# led.net
KiCad netlist of a schematic drawn in Altium Designer
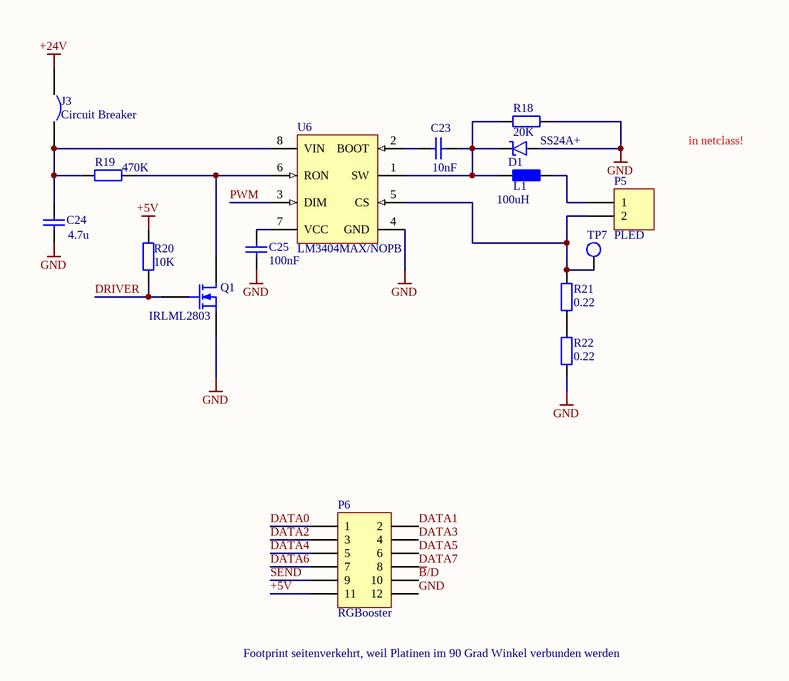
[diagram p0: led.SchDoc]

(export (version "E")
  (design (tool "Eeschema 10.0.6"))
  (components
    (comp (ref "C23")
      (value "10nF")
      (footprint "6-0805_M")
      (description "Capacitor")
      (fields (field (name "Comment") "Cap") (field (name "PUBLISHER") "Altium Limited"))
      (libsource (lib "Miscellaneous Devices") (part "Cap"))
    )
    (comp (ref "C24")
      (value "4.7u")
      (footprint "C1206")
      (description "Capacitor")
      (fields (field (name "Comment") "Cap") (field (name "PUBLISHER") "Altium Limited"))
      (libsource (lib "Miscellaneous Devices") (part "Cap"))
    )
    (comp (ref "C25")
      (value "100nF")
      (footprint "6-0805_M")
      (description "Capacitor")
      (fields (field (name "Comment") "Cap") (field (name "PUBLISHER") "Altium Limited"))
      (libsource (lib "Miscellaneous Devices") (part "Cap"))
    )
    (comp (ref "D1") (value "SS24A+") (footprint "DO-214AC") (libsource (lib "clusterlib") (part "Schottky")))
    (comp (ref "J3")
      (value "Circuit Breaker")
      (footprint "SOLDER_JUMPER_24mil")
      (fields (field (name "PUBLISHER") "Altium Limited"))
      (libsource (lib "Miscellaneous Devices") (part "Circuit Breaker"))
    )
    (comp (ref "L1")
      (value "100uH")
      (footprint "ELLCTP")
      (fields (field (name "Comment") "Ind"))
      (libsource (lib "clusterlib") (part "Inductor"))
    )
    (comp (ref "P5")
      (value "PLED")
      (footprint "HDR1X2")
      (description "Header, 2-Pin")
      (fields (field (name "PUBLISHER") "Altium Limited"))
      (libsource (lib "Miscellaneous Connectors") (part "Header 2"))
    )
    (comp (ref "P6")
      (value "RGBooster")
      (footprint "KLEMME_SEITENVERKEHRT")
      (description "Header, 6-Pin, Dual row")
      (fields (field (name "PUBLISHER") "Altium Limited"))
      (libsource (lib "Miscellaneous Connectors") (part "Header 6X2"))
    )
    (comp (ref "Q1")
      (value "IRLML2803")
      (footprint "SOT-23_N")
      (description "N-Channel MOSFET")
      (fields (field (name "PUBLISHER") "Altium Limited"))
      (libsource (lib "Miscellaneous Devices") (part "MOSFET-N"))
    )
    (comp (ref "R18")
      (value "20K")
      (footprint "6-0805_M")
      (description "Resistor")
      (fields (field (name "Comment") "Res2") (field (name "PUBLISHER") "Altium Limited"))
      (libsource (lib "") (part "Res2_1"))
    )
    (comp (ref "R19")
      (value "470K")
      (footprint "6-0805_M")
      (description "Resistor")
      (fields (field (name "Comment") "Res2") (field (name "PUBLISHER") "Altium Limited"))
      (libsource (lib "") (part "Res2_2"))
    )
    (comp (ref "R20")
      (value "10K")
      (footprint "6-0805_M")
      (description "Resistor")
      (fields (field (name "Comment") "Res2") (field (name "PUBLISHER") "Altium Limited"))
      (libsource (lib "Miscellaneous Devices") (part "Res2"))
    )
    (comp (ref "R21")
      (value "0.22")
      (footprint "C1206")
      (description "Resistor")
      (fields (field (name "Comment") "Res2") (field (name "PUBLISHER") "Altium Limited"))
      (libsource (lib "Miscellaneous Devices") (part "Res2"))
    )
    (comp (ref "R22")
      (value "0.22")
      (footprint "C1206")
      (description "Resistor")
      (fields (field (name "Comment") "Res2") (field (name "PUBLISHER") "Altium Limited"))
      (libsource (lib "Miscellaneous Devices") (part "Res2"))
    )
    (comp (ref "TP7")
      (value "TestPoint")
      (footprint "MEASUREMENT_POINT")
      (description "Testpoint")
      (libsource (lib "clusterlib") (part "TestPoint"))
    )
    (comp (ref "U6")
      (value "LM3404MAX/NOPB")
      (footprint "M08A_N")
      (description "1.0A Constant Current Buck Regulator for High Power LED Drivers, 8-pin Narrow SOIC, Pb-Free")
      (fields (field (name "MANUFACTURER") "National Semiconductor"))
      (libsource (lib "National Semiconductor MiscPower") (part "LM3404MAX/NOPB"))
    )
  )
  (nets
    (net (code "1") (name "+5V") (class "Default")
      (node (ref "P6") (pin "11") (pinfunction "11_11") (pintype "passive"))
      (node (ref "R20") (pin "2") (pinfunction "2_2") (pintype "passive"))
    )
    (net (code "2") (name "+24V") (class "Default")
      (node (ref "J3") (pin "1") (pinfunction "1_1") (pintype "passive"))
    )
    (net (code "3") (name "/DATA0") (class "Default")
      (node (ref "P6") (pin "1") (pinfunction "1_1") (pintype "passive"))
    )
    (net (code "4") (name "/DATA1") (class "Default")
      (node (ref "P6") (pin "2") (pinfunction "2_2") (pintype "passive"))
    )
    (net (code "5") (name "/DATA2") (class "Default")
      (node (ref "P6") (pin "3") (pinfunction "3_3") (pintype "passive"))
    )
    (net (code "6") (name "/DATA3") (class "Default")
      (node (ref "P6") (pin "4") (pinfunction "4_4") (pintype "passive"))
    )
    (net (code "7") (name "/DATA4") (class "Default")
      (node (ref "P6") (pin "5") (pinfunction "5_5") (pintype "passive"))
    )
    (net (code "8") (name "/DATA5") (class "Default")
      (node (ref "P6") (pin "6") (pinfunction "6_6") (pintype "passive"))
    )
    (net (code "9") (name "/DATA6") (class "Default")
      (node (ref "P6") (pin "7") (pinfunction "7_7") (pintype "passive"))
    )
    (net (code "10") (name "/DATA7") (class "Default")
      (node (ref "P6") (pin "8") (pinfunction "8_8") (pintype "passive"))
    )
    (net (code "11") (name "/DRIVER") (class "Default")
      (node (ref "Q1") (pin "2") (pinfunction "G_2") (pintype "passive"))
      (node (ref "R20") (pin "1") (pinfunction "1_1") (pintype "passive"))
    )
    (net (code "12") (name "/PWM") (class "Default")
      (node (ref "U6") (pin "3") (pinfunction "DIM_3") (pintype "input"))
    )
    (net (code "13") (name "/SEND") (class "Default")
      (node (ref "P6") (pin "9") (pinfunction "9_9") (pintype "passive"))
    )
    (net (code "14") (name "/~{B}{slash}D") (class "Default")
      (node (ref "P6") (pin "10") (pinfunction "10_10") (pintype "passive"))
    )
    (net (code "15") (name "GND") (class "Default")
      (node (ref "C24") (pin "1") (pinfunction "1_1") (pintype "passive"))
      (node (ref "C25") (pin "1") (pinfunction "1_1") (pintype "passive"))
      (node (ref "D1") (pin "1") (pinfunction "A_1") (pintype "passive"))
      (node (ref "P6") (pin "12") (pinfunction "12_12") (pintype "passive"))
      (node (ref "Q1") (pin "3") (pinfunction "S_3") (pintype "passive"))
      (node (ref "R18") (pin "1") (pinfunction "1_1") (pintype "passive"))
      (node (ref "R22") (pin "1") (pinfunction "1_1") (pintype "passive"))
      (node (ref "U6") (pin "4") (pinfunction "GND_4") (pintype "power_in"))
    )
    (net (code "16") (name "Net-(D1-K)") (class "Default")
      (node (ref "C23") (pin "2") (pinfunction "2_2") (pintype "passive"))
      (node (ref "D1") (pin "2") (pinfunction "K_2") (pintype "passive"))
      (node (ref "L1") (pin "1") (pinfunction "1_1") (pintype "passive"))
      (node (ref "R18") (pin "2") (pinfunction "2_2") (pintype "passive"))
      (node (ref "U6") (pin "1") (pinfunction "SW_1") (pintype "power_in"))
    )
    (net (code "17") (name "Net-(L1-Pad2)") (class "Default")
      (node (ref "L1") (pin "2") (pinfunction "2_2") (pintype "passive"))
      (node (ref "P5") (pin "1") (pinfunction "1_1") (pintype "passive"))
    )
    (net (code "18") (name "Net-(Q1-D)") (class "Default")
      (node (ref "Q1") (pin "1") (pinfunction "D_1") (pintype "passive"))
      (node (ref "R19") (pin "2") (pinfunction "2_2") (pintype "passive"))
      (node (ref "U6") (pin "6") (pinfunction "RON_6") (pintype "input"))
    )
    (net (code "19") (name "Net-(R21-Pad1)") (class "Default")
      (node (ref "R21") (pin "1") (pinfunction "1_1") (pintype "passive"))
      (node (ref "R22") (pin "2") (pinfunction "2_2") (pintype "passive"))
    )
    (net (code "20") (name "Net-(U6-BOOT)") (class "Default")
      (node (ref "C23") (pin "1") (pinfunction "1_1") (pintype "passive"))
      (node (ref "U6") (pin "2") (pinfunction "BOOT_2") (pintype "input"))
    )
    (net (code "21") (name "Net-(U6-CS)") (class "Default")
      (node (ref "P5") (pin "2") (pinfunction "2_2") (pintype "passive"))
      (node (ref "R21") (pin "2") (pinfunction "2_2") (pintype "passive"))
      (node (ref "TP7") (pin "1") (pinfunction "1_1") (pintype "passive"))
      (node (ref "U6") (pin "5") (pinfunction "CS_5") (pintype "input"))
    )
    (net (code "22") (name "Net-(U6-VCC)") (class "Default")
      (node (ref "C25") (pin "2") (pinfunction "2_2") (pintype "passive"))
      (node (ref "U6") (pin "7") (pinfunction "VCC_7") (pintype "power_in"))
    )
    (net (code "23") (name "Net-(U6-VIN)") (class "Default")
      (node (ref "C24") (pin "2") (pinfunction "2_2") (pintype "passive"))
      (node (ref "J3") (pin "2") (pinfunction "2_2") (pintype "passive"))
      (node (ref "R19") (pin "1") (pinfunction "1_1") (pintype "passive"))
      (node (ref "U6") (pin "8") (pinfunction "VIN_8") (pintype "power_in"))
    )
  )
)
